# Motor_Control.net
KiCad netlist of a schematic drawn in Altium Designer
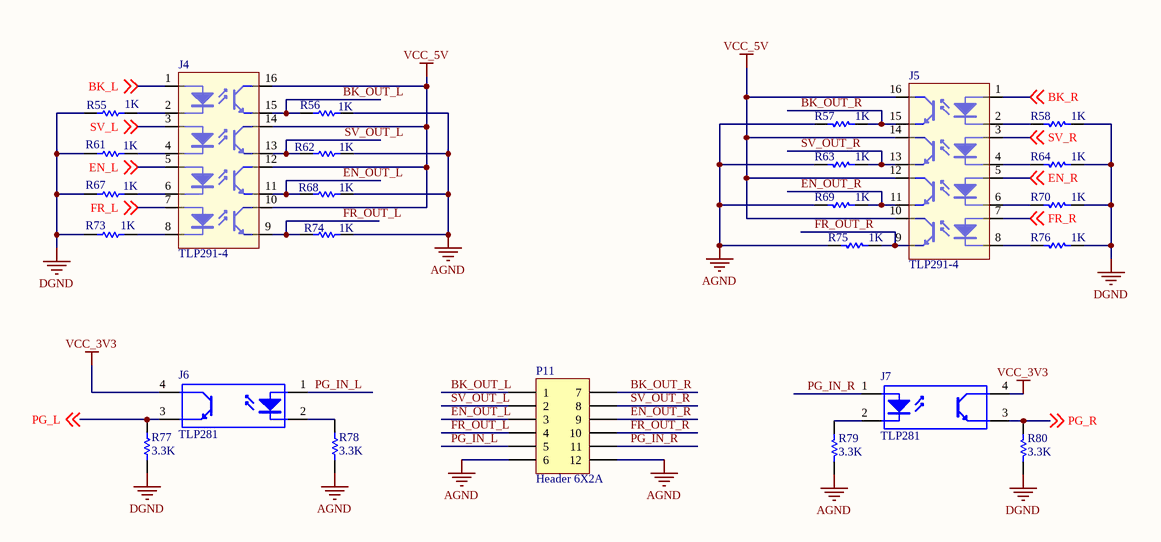
[diagram p0: Motor Control.SchDoc]

(export (version "E")
  (design (tool "Eeschema 10.0.6"))
  (components
    (comp (ref "J4")
      (value "TLP291-4")
      (footprint "SOIC127P700X210-16N")
      (description "光耦")
      (libsource (lib "fszhang") (part "TLP291-4"))
    )
    (comp (ref "J5")
      (value "TLP291-4")
      (footprint "SOIC127P700X210-16N")
      (description "光耦")
      (libsource (lib "fszhang") (part "TLP291-4"))
    )
    (comp (ref "J6")
      (value "TLP281")
      (footprint "SOP127P710X350-4N")
      (description "光耦")
      (fields (field (name "PUBLISHER") "Altium Limited"))
      (libsource (lib "Fszhang") (part "TLP281"))
    )
    (comp (ref "J7")
      (value "TLP281")
      (footprint "SOP127P710X350-4N")
      (description "光耦")
      (fields (field (name "PUBLISHER") "Altium Limited"))
      (libsource (lib "fszhang") (part "TLP281"))
    )
    (comp (ref "P11")
      (value "Header 6X2A")
      (footprint "Molex-12P")
      (description "Header, 6-Pin, Dual row")
      (fields (field (name "PUBLISHER") "Altium Limited"))
      (libsource (lib "Miscellaneous Connectors") (part "Header 6X2A"))
    )
    (comp (ref "R55")
      (value "1K")
      (footprint "R0805")
      (description "Resistor")
      (fields (field (name "Comment") "Res1") (field (name "PUBLISHER") "Altium Limited"))
      (libsource (lib "boocax_schlib") (part "Res1"))
    )
    (comp (ref "R56")
      (value "1K")
      (footprint "R0805")
      (description "Resistor")
      (fields (field (name "Comment") "Res1") (field (name "PUBLISHER") "Altium Limited"))
      (libsource (lib "boocax_schlib") (part "Res1"))
    )
    (comp (ref "R57")
      (value "1K")
      (footprint "R0805")
      (description "Resistor")
      (fields (field (name "Comment") "Res1") (field (name "PUBLISHER") "Altium Limited"))
      (libsource (lib "boocax_schlib") (part "Res1"))
    )
    (comp (ref "R58")
      (value "1K")
      (footprint "R0805")
      (description "Resistor")
      (fields (field (name "Comment") "Res1") (field (name "PUBLISHER") "Altium Limited"))
      (libsource (lib "boocax_schlib") (part "Res1"))
    )
    (comp (ref "R61")
      (value "1K")
      (footprint "R0805")
      (description "Resistor")
      (fields (field (name "Comment") "Res1") (field (name "PUBLISHER") "Altium Limited"))
      (libsource (lib "boocax_schlib") (part "Res1"))
    )
    (comp (ref "R62")
      (value "1K")
      (footprint "R0805")
      (description "Resistor")
      (fields (field (name "Comment") "Res1") (field (name "PUBLISHER") "Altium Limited"))
      (libsource (lib "boocax_schlib") (part "Res1"))
    )
    (comp (ref "R63")
      (value "1K")
      (footprint "R0805")
      (description "Resistor")
      (fields (field (name "Comment") "Res1") (field (name "PUBLISHER") "Altium Limited"))
      (libsource (lib "boocax_schlib") (part "Res1"))
    )
    (comp (ref "R64")
      (value "1K")
      (footprint "R0805")
      (description "Resistor")
      (fields (field (name "Comment") "Res1") (field (name "PUBLISHER") "Altium Limited"))
      (libsource (lib "boocax_schlib") (part "Res1"))
    )
    (comp (ref "R67")
      (value "1K")
      (footprint "R0805")
      (description "Resistor")
      (fields (field (name "Comment") "Res1") (field (name "PUBLISHER") "Altium Limited"))
      (libsource (lib "boocax_schlib") (part "Res1"))
    )
    (comp (ref "R68")
      (value "1K")
      (footprint "R0805")
      (description "Resistor")
      (fields (field (name "Comment") "Res1") (field (name "PUBLISHER") "Altium Limited"))
      (libsource (lib "boocax_schlib") (part "Res1"))
    )
    (comp (ref "R69")
      (value "1K")
      (footprint "R0805")
      (description "Resistor")
      (fields (field (name "Comment") "Res1") (field (name "PUBLISHER") "Altium Limited"))
      (libsource (lib "boocax_schlib") (part "Res1"))
    )
    (comp (ref "R70")
      (value "1K")
      (footprint "R0805")
      (description "Resistor")
      (fields (field (name "Comment") "Res1") (field (name "PUBLISHER") "Altium Limited"))
      (libsource (lib "boocax_schlib") (part "Res1"))
    )
    (comp (ref "R73")
      (value "1K")
      (footprint "R0805")
      (description "Resistor")
      (fields (field (name "Comment") "Res1") (field (name "PUBLISHER") "Altium Limited"))
      (libsource (lib "boocax_schlib") (part "Res1"))
    )
    (comp (ref "R74")
      (value "1K")
      (footprint "R0805")
      (description "Resistor")
      (fields (field (name "Comment") "Res1") (field (name "PUBLISHER") "Altium Limited"))
      (libsource (lib "boocax_schlib") (part "Res1"))
    )
    (comp (ref "R75")
      (value "1K")
      (footprint "R0805")
      (description "Resistor")
      (fields (field (name "Comment") "Res1") (field (name "PUBLISHER") "Altium Limited"))
      (libsource (lib "boocax_schlib") (part "Res1"))
    )
    (comp (ref "R76")
      (value "1K")
      (footprint "R0805")
      (description "Resistor")
      (fields (field (name "Comment") "Res1") (field (name "PUBLISHER") "Altium Limited"))
      (libsource (lib "boocax_schlib") (part "Res1"))
    )
    (comp (ref "R77")
      (value "3.3K")
      (footprint "R0805")
      (description "Resistor")
      (fields (field (name "Comment") "Res1") (field (name "PUBLISHER") "Altium Limited"))
      (libsource (lib "") (part "Res1_1"))
    )
    (comp (ref "R78")
      (value "3.3K")
      (footprint "R0805")
      (description "Resistor")
      (fields (field (name "Comment") "Res1") (field (name "PUBLISHER") "Altium Limited"))
      (libsource (lib "boocax_schlib") (part "Res1"))
    )
    (comp (ref "R79")
      (value "3.3K")
      (footprint "R0805")
      (description "Resistor")
      (fields (field (name "Comment") "Res1") (field (name "PUBLISHER") "Altium Limited"))
      (libsource (lib "boocax_schlib") (part "Res1"))
    )
    (comp (ref "R80")
      (value "3.3K")
      (footprint "R0805")
      (description "Resistor")
      (fields (field (name "Comment") "Res1") (field (name "PUBLISHER") "Altium Limited"))
      (libsource (lib "boocax_schlib") (part "Res1"))
    )
  )
  (nets
    (net (code "9") (name "/BK_OUT_L") (class "Default")
      (node (ref "J4") (pin "15") (pinfunction "E_15") (pintype "passive"))
      (node (ref "P11") (pin "1") (pinfunction "1_1") (pintype "passive"))
      (node (ref "R56") (pin "1") (pinfunction "1_1") (pintype "passive"))
    )
    (net (code "10") (name "/BK_OUT_R") (class "Default")
      (node (ref "J5") (pin "15") (pinfunction "E_15") (pintype "passive"))
      (node (ref "P11") (pin "7") (pinfunction "7_7") (pintype "passive"))
      (node (ref "R57") (pin "1") (pinfunction "1_1") (pintype "passive"))
    )
    (net (code "15") (name "/EN_OUT_L") (class "Default")
      (node (ref "J4") (pin "11") (pinfunction "E_11") (pintype "passive"))
      (node (ref "P11") (pin "3") (pinfunction "3_3") (pintype "passive"))
      (node (ref "R68") (pin "1") (pinfunction "1_1") (pintype "passive"))
    )
    (net (code "16") (name "/EN_OUT_R") (class "Default")
      (node (ref "J5") (pin "11") (pinfunction "E_11") (pintype "passive"))
      (node (ref "P11") (pin "9") (pinfunction "9_9") (pintype "passive"))
      (node (ref "R69") (pin "1") (pinfunction "1_1") (pintype "passive"))
    )
    (net (code "18") (name "/FR_OUT_L") (class "Default")
      (node (ref "J4") (pin "9") (pinfunction "E_9") (pintype "passive"))
      (node (ref "P11") (pin "4") (pinfunction "4_4") (pintype "passive"))
      (node (ref "R74") (pin "1") (pinfunction "1_1") (pintype "passive"))
    )
    (net (code "19") (name "/FR_OUT_R") (class "Default")
      (node (ref "J5") (pin "9") (pinfunction "E_9") (pintype "passive"))
      (node (ref "P11") (pin "10") (pinfunction "10_10") (pintype "passive"))
      (node (ref "R75") (pin "1") (pinfunction "1_1") (pintype "passive"))
    )
    (net (code "20") (name "/PG_IN_L") (class "Default")
      (node (ref "J6") (pin "1") (pinfunction "A_1") (pintype "passive"))
      (node (ref "P11") (pin "5") (pinfunction "5_5") (pintype "passive"))
    )
    (net (code "21") (name "/PG_IN_R") (class "Default")
      (node (ref "J7") (pin "1") (pinfunction "A_1") (pintype "passive"))
      (node (ref "P11") (pin "11") (pinfunction "11_11") (pintype "passive"))
    )
    (net (code "24") (name "/SV_OUT_L") (class "Default")
      (node (ref "J4") (pin "13") (pinfunction "E_13") (pintype "passive"))
      (node (ref "P11") (pin "2") (pinfunction "2_2") (pintype "passive"))
      (node (ref "R62") (pin "1") (pinfunction "1_1") (pintype "passive"))
    )
    (net (code "25") (name "/SV_OUT_R") (class "Default")
      (node (ref "J5") (pin "13") (pinfunction "E_13") (pintype "passive"))
      (node (ref "P11") (pin "8") (pinfunction "8_8") (pintype "passive"))
      (node (ref "R63") (pin "1") (pinfunction "1_1") (pintype "passive"))
    )
    (net (code "28") (name "AGND") (class "Default")
      (node (ref "P11") (pin "12") (pinfunction "12_12") (pintype "passive"))
      (node (ref "P11") (pin "6") (pinfunction "6_6") (pintype "passive"))
      (node (ref "R56") (pin "2") (pinfunction "2_2") (pintype "passive"))
      (node (ref "R57") (pin "2") (pinfunction "2_2") (pintype "passive"))
      (node (ref "R62") (pin "2") (pinfunction "2_2") (pintype "passive"))
      (node (ref "R63") (pin "2") (pinfunction "2_2") (pintype "passive"))
      (node (ref "R68") (pin "2") (pinfunction "2_2") (pintype "passive"))
      (node (ref "R69") (pin "2") (pinfunction "2_2") (pintype "passive"))
      (node (ref "R74") (pin "2") (pinfunction "2_2") (pintype "passive"))
      (node (ref "R75") (pin "2") (pinfunction "2_2") (pintype "passive"))
      (node (ref "R78") (pin "2") (pinfunction "2_2") (pintype "passive"))
      (node (ref "R79") (pin "2") (pinfunction "2_2") (pintype "passive"))
    )
    (net (code "29") (name "BK_L") (class "Default")
      (node (ref "J4") (pin "1") (pinfunction "A_1") (pintype "passive"))
    )
    (net (code "30") (name "BK_R") (class "Default")
      (node (ref "J5") (pin "1") (pinfunction "A_1") (pintype "passive"))
    )
    (net (code "31") (name "DGND") (class "Default")
      (node (ref "R55") (pin "2") (pinfunction "2_2") (pintype "passive"))
      (node (ref "R58") (pin "2") (pinfunction "2_2") (pintype "passive"))
      (node (ref "R61") (pin "2") (pinfunction "2_2") (pintype "passive"))
      (node (ref "R64") (pin "2") (pinfunction "2_2") (pintype "passive"))
      (node (ref "R67") (pin "2") (pinfunction "2_2") (pintype "passive"))
      (node (ref "R70") (pin "2") (pinfunction "2_2") (pintype "passive"))
      (node (ref "R73") (pin "2") (pinfunction "2_2") (pintype "passive"))
      (node (ref "R76") (pin "2") (pinfunction "2_2") (pintype "passive"))
      (node (ref "R77") (pin "1") (pinfunction "1_1") (pintype "passive"))
      (node (ref "R80") (pin "2") (pinfunction "2_2") (pintype "passive"))
    )
    (net (code "32") (name "EN_L") (class "Default")
      (node (ref "J4") (pin "5") (pinfunction "A_5") (pintype "passive"))
    )
    (net (code "33") (name "EN_R") (class "Default")
      (node (ref "J5") (pin "5") (pinfunction "A_5") (pintype "passive"))
    )
    (net (code "34") (name "FR_L") (class "Default")
      (node (ref "J4") (pin "7") (pinfunction "A_7") (pintype "passive"))
    )
    (net (code "35") (name "FR_R") (class "Default")
      (node (ref "J5") (pin "7") (pinfunction "A_7") (pintype "passive"))
    )
    (net (code "36") (name "Net-(J4-K-Pad2)") (class "Default")
      (node (ref "J4") (pin "2") (pinfunction "K_2") (pintype "passive"))
      (node (ref "R55") (pin "1") (pinfunction "1_1") (pintype "passive"))
    )
    (net (code "37") (name "Net-(J4-K-Pad4)") (class "Default")
      (node (ref "J4") (pin "4") (pinfunction "K_4") (pintype "passive"))
      (node (ref "R61") (pin "1") (pinfunction "1_1") (pintype "passive"))
    )
    (net (code "38") (name "Net-(J4-K-Pad6)") (class "Default")
      (node (ref "J4") (pin "6") (pinfunction "K_6") (pintype "passive"))
      (node (ref "R67") (pin "1") (pinfunction "1_1") (pintype "passive"))
    )
    (net (code "39") (name "Net-(J4-K-Pad8)") (class "Default")
      (node (ref "J4") (pin "8") (pinfunction "K_8") (pintype "passive"))
      (node (ref "R73") (pin "1") (pinfunction "1_1") (pintype "passive"))
    )
    (net (code "40") (name "Net-(J5-K-Pad2)") (class "Default")
      (node (ref "J5") (pin "2") (pinfunction "K_2") (pintype "passive"))
      (node (ref "R58") (pin "1") (pinfunction "1_1") (pintype "passive"))
    )
    (net (code "41") (name "Net-(J5-K-Pad4)") (class "Default")
      (node (ref "J5") (pin "4") (pinfunction "K_4") (pintype "passive"))
      (node (ref "R64") (pin "1") (pinfunction "1_1") (pintype "passive"))
    )
    (net (code "42") (name "Net-(J5-K-Pad6)") (class "Default")
      (node (ref "J5") (pin "6") (pinfunction "K_6") (pintype "passive"))
      (node (ref "R70") (pin "1") (pinfunction "1_1") (pintype "passive"))
    )
    (net (code "43") (name "Net-(J5-K-Pad8)") (class "Default")
      (node (ref "J5") (pin "8") (pinfunction "K_8") (pintype "passive"))
      (node (ref "R76") (pin "1") (pinfunction "1_1") (pintype "passive"))
    )
    (net (code "44") (name "Net-(J6-K)") (class "Default")
      (node (ref "J6") (pin "2") (pinfunction "K_2") (pintype "passive"))
      (node (ref "R78") (pin "1") (pinfunction "1_1") (pintype "passive"))
    )
    (net (code "45") (name "Net-(J7-K)") (class "Default")
      (node (ref "J7") (pin "2") (pinfunction "K_2") (pintype "passive"))
      (node (ref "R79") (pin "1") (pinfunction "1_1") (pintype "passive"))
    )
    (net (code "46") (name "PG_L") (class "Default")
      (node (ref "J6") (pin "3") (pinfunction "E_3") (pintype "passive"))
      (node (ref "R77") (pin "2") (pinfunction "2_2") (pintype "passive"))
    )
    (net (code "47") (name "PG_R") (class "Default")
      (node (ref "J7") (pin "3") (pinfunction "E_3") (pintype "passive"))
      (node (ref "R80") (pin "1") (pinfunction "1_1") (pintype "passive"))
    )
    (net (code "48") (name "SV_L") (class "Default")
      (node (ref "J4") (pin "3") (pinfunction "A_3") (pintype "passive"))
    )
    (net (code "49") (name "SV_R") (class "Default")
      (node (ref "J5") (pin "3") (pinfunction "A_3") (pintype "passive"))
    )
    (net (code "50") (name "VCC_3V3") (class "Default")
      (node (ref "J6") (pin "4") (pinfunction "C_4") (pintype "passive"))
      (node (ref "J7") (pin "4") (pinfunction "C_4") (pintype "passive"))
    )
    (net (code "51") (name "VCC_5V") (class "Default")
      (node (ref "J4") (pin "10") (pinfunction "C_10") (pintype "passive"))
      (node (ref "J4") (pin "12") (pinfunction "C_12") (pintype "passive"))
      (node (ref "J4") (pin "14") (pinfunction "C_14") (pintype "passive"))
      (node (ref "J4") (pin "16") (pinfunction "C_16") (pintype "passive"))
      (node (ref "J5") (pin "10") (pinfunction "C_10") (pintype "passive"))
      (node (ref "J5") (pin "12") (pinfunction "C_12") (pintype "passive"))
      (node (ref "J5") (pin "14") (pinfunction "C_14") (pintype "passive"))
      (node (ref "J5") (pin "16") (pinfunction "C_16") (pintype "passive"))
    )
  )
)
